# atxpd.net
KiCad netlist of a schematic drawn in EAGLE
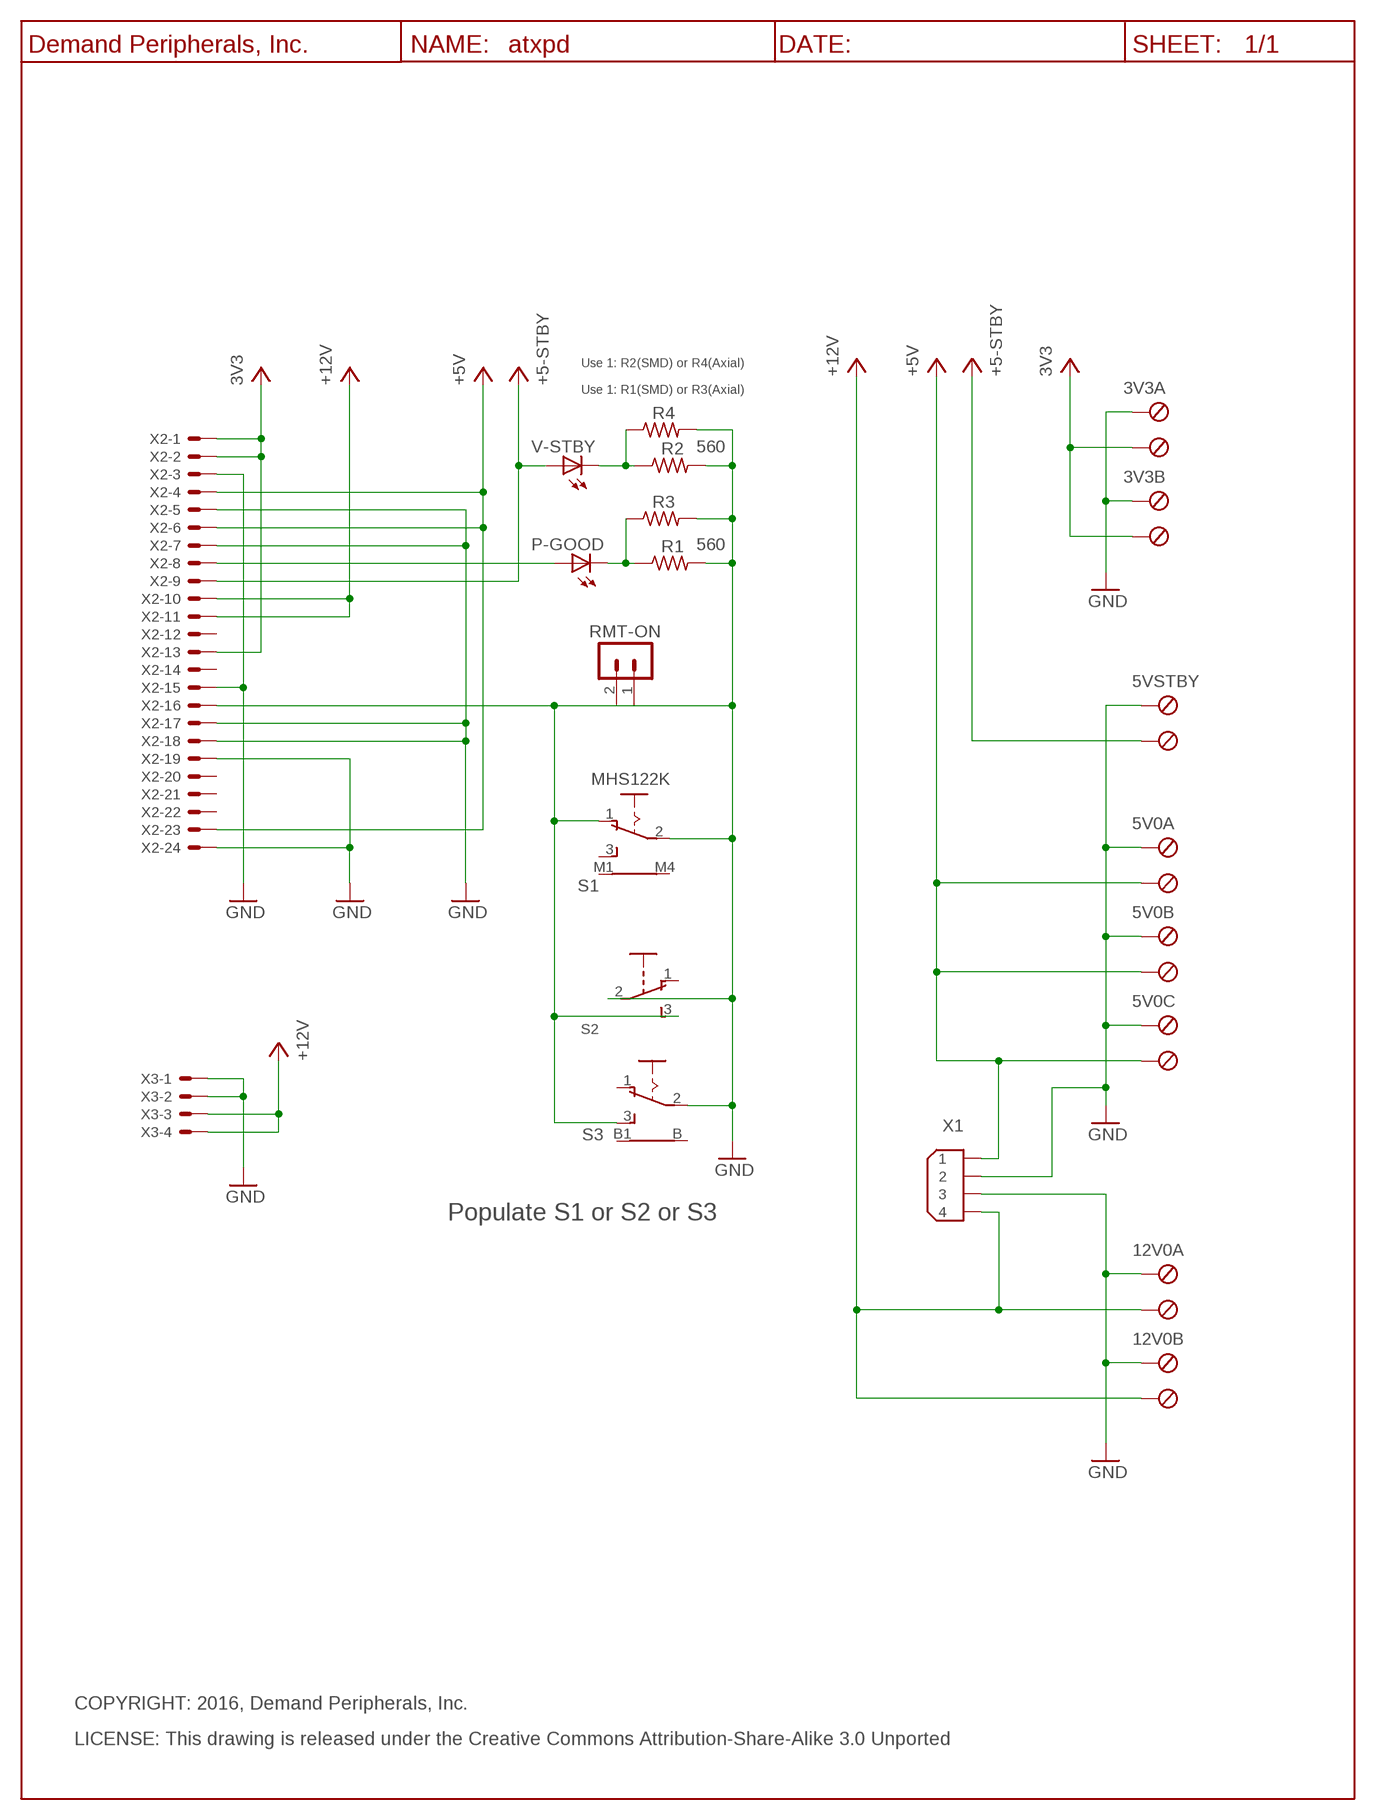
[diagram p0: schematic, sheet 1]

(export (version "E")
  (design (tool "Eeschema 10.0.6"))
  (components
    (comp (ref "3V3A")
      (value "TBLK-5.08-X2")
      (footprint "eagle-import:TBLK-5.08-X2")
      (libsource (lib "eagle-import") (part "TBLK-5.08-X2"))
    )
    (comp (ref "3V3B")
      (value "TBLK-5.08-X2")
      (footprint "eagle-import:TBLK-5.08-X2")
      (libsource (lib "eagle-import") (part "TBLK-5.08-X2"))
    )
    (comp (ref "5V0A")
      (value "TBLK-5.08-X2")
      (footprint "eagle-import:TBLK-5.08-X2")
      (libsource (lib "eagle-import") (part "TBLK-5.08-X2"))
    )
    (comp (ref "5V0B")
      (value "TBLK-5.08-X2")
      (footprint "eagle-import:TBLK-5.08-X2")
      (libsource (lib "eagle-import") (part "TBLK-5.08-X2"))
    )
    (comp (ref "5V0C")
      (value "TBLK-5.08-X2")
      (footprint "eagle-import:TBLK-5.08-X2")
      (libsource (lib "eagle-import") (part "TBLK-5.08-X2"))
    )
    (comp (ref "5VSTBY")
      (value "TBLK-5.08-X2")
      (footprint "eagle-import:TBLK-5.08-X2")
      (libsource (lib "eagle-import") (part "TBLK-5.08-X2"))
    )
    (comp (ref "12V0A")
      (value "TBLK-5.08-X2")
      (footprint "eagle-import:TBLK-5.08-X2")
      (libsource (lib "eagle-import") (part "TBLK-5.08-X2"))
    )
    (comp (ref "12V0B")
      (value "TBLK-5.08-X2")
      (footprint "eagle-import:TBLK-5.08-X2")
      (libsource (lib "eagle-import") (part "TBLK-5.08-X2"))
    )
    (comp (ref "P-GOOD")
      (value "3mm_LED")
      (footprint "eagle-import:LED5MM")
      (libsource (lib "eagle-import") (part "LED-5MM-RED"))
    )
    (comp (ref "R1")
      (value "560")
      (footprint "eagle-import:R0603")
      (libsource (lib "eagle-import") (part "R560_R0603"))
    )
    (comp (ref "R2")
      (value "560")
      (footprint "eagle-import:R0603")
      (libsource (lib "eagle-import") (part "R560_R0603"))
    )
    (comp (ref "R3")
      (value "560")
      (footprint "eagle-import:R4TENTHS")
      (libsource (lib "eagle-import") (part "R560_"))
    )
    (comp (ref "R4")
      (value "560")
      (footprint "eagle-import:R4TENTHS")
      (libsource (lib "eagle-import") (part "R560_"))
    )
    (comp (ref "RMT-ON")
      (value "PinHdr254-2")
      (footprint "eagle-import:HDR-2X1")
      (libsource (lib "eagle-import") (part "HDR-2X1-LCK"))
    )
    (comp (ref "S1")
      (value "MHS122K")
      (footprint "eagle-import:MHS122K")
      (libsource (lib "eagle-import") (part "MHS122K"))
    )
    (comp (ref "S2")
      (value "TINYTOGGLE-SPDT-TH")
      (footprint "eagle-import:SPDT-TENTHINCH")
      (libsource (lib "eagle-import") (part "TINYTOGGLE-SPDT-TH"))
    )
    (comp (ref "S3")
      (value "Vert_SW(Option)")
      (footprint "eagle-import:TOGGLE_SPDT_PC")
      (libsource (lib "eagle-import") (part "TOGGLE_SPDT_PC"))
    )
    (comp (ref "U$1")
      (value "DP_FRAME_P")
      (footprint "eagle-import:LETTER_P")
      (libsource (lib "eagle-import") (part "DP_FRAME_P"))
    )
    (comp (ref "V-STBY")
      (value "3mm_LED")
      (footprint "eagle-import:LED5MM")
      (libsource (lib "eagle-import") (part "LED-5MM-GRN"))
    )
    (comp (ref "X1")
      (value "9090-4V")
      (footprint "eagle-import:9090-4V")
      (libsource (lib "eagle-import") (part "9090-4V"))
    )
    (comp (ref "X2")
      (value "ATX_Std")
      (footprint "eagle-import:5566-24MOD")
      (libsource (lib "eagle-import") (part "5566-24MOD"))
    )
    (comp (ref "X3")
      (value "ATX_Plus4")
      (footprint "eagle-import:5566-4MOD")
      (libsource (lib "eagle-import") (part "5566-4MOD"))
    )
  )
  (nets
    (net (code "1") (name "+5-STBY") (class "Default")
      (node (ref "5VSTBY") (pin "2") (pinfunction "KL1_2") (pintype "passive"))
      (node (ref "V-STBY") (pin "A") (pinfunction "A_A") (pintype "passive"))
      (node (ref "X2") (pin "9") (pinfunction "S_9") (pintype "passive"))
    )
    (net (code "2") (name "+5V") (class "Default")
      (node (ref "5V0A") (pin "2") (pinfunction "KL1_2") (pintype "passive"))
      (node (ref "5V0B") (pin "2") (pinfunction "KL1_2") (pintype "passive"))
      (node (ref "5V0C") (pin "2") (pinfunction "KL1_2") (pintype "passive"))
      (node (ref "X1") (pin "1") (pinfunction "1_1") (pintype "passive"))
      (node (ref "X2") (pin "23") (pinfunction "S_23") (pintype "passive"))
      (node (ref "X2") (pin "4") (pinfunction "S_4") (pintype "passive"))
      (node (ref "X2") (pin "6") (pinfunction "S_6") (pintype "passive"))
    )
    (net (code "3") (name "+12V") (class "Default")
      (node (ref "12V0A") (pin "2") (pinfunction "KL1_2") (pintype "passive"))
      (node (ref "12V0B") (pin "2") (pinfunction "KL1_2") (pintype "passive"))
      (node (ref "X1") (pin "4") (pinfunction "4_4") (pintype "passive"))
      (node (ref "X2") (pin "10") (pinfunction "S_10") (pintype "passive"))
      (node (ref "X2") (pin "11") (pinfunction "S_11") (pintype "passive"))
      (node (ref "X3") (pin "3") (pinfunction "S_3") (pintype "passive"))
      (node (ref "X3") (pin "4") (pinfunction "S_4") (pintype "passive"))
    )
    (net (code "4") (name "3V3") (class "Default")
      (node (ref "3V3A") (pin "2") (pinfunction "KL1_2") (pintype "passive"))
      (node (ref "3V3B") (pin "2") (pinfunction "KL1_2") (pintype "passive"))
      (node (ref "X2") (pin "1") (pinfunction "S_1") (pintype "passive"))
      (node (ref "X2") (pin "13") (pinfunction "S_13") (pintype "passive"))
      (node (ref "X2") (pin "2") (pinfunction "S_2") (pintype "passive"))
    )
    (net (code "5") (name "GND") (class "Default")
      (node (ref "12V0A") (pin "1") (pinfunction "KL_1") (pintype "passive"))
      (node (ref "12V0B") (pin "1") (pinfunction "KL_1") (pintype "passive"))
      (node (ref "3V3A") (pin "1") (pinfunction "KL_1") (pintype "passive"))
      (node (ref "3V3B") (pin "1") (pinfunction "KL_1") (pintype "passive"))
      (node (ref "5V0A") (pin "1") (pinfunction "KL_1") (pintype "passive"))
      (node (ref "5V0B") (pin "1") (pinfunction "KL_1") (pintype "passive"))
      (node (ref "5V0C") (pin "1") (pinfunction "KL_1") (pintype "passive"))
      (node (ref "5VSTBY") (pin "1") (pinfunction "KL_1") (pintype "passive"))
      (node (ref "R1") (pin "2") (pinfunction "2_2") (pintype "passive"))
      (node (ref "R2") (pin "2") (pinfunction "2_2") (pintype "passive"))
      (node (ref "R3") (pin "2") (pinfunction "2_2") (pintype "passive"))
      (node (ref "R4") (pin "2") (pinfunction "2_2") (pintype "passive"))
      (node (ref "RMT-ON") (pin "2") (pinfunction "1_2") (pintype "passive"))
      (node (ref "S1") (pin "2") (pinfunction "P_2") (pintype "passive"))
      (node (ref "S2") (pin "2") (pinfunction "2_2") (pintype "passive"))
      (node (ref "S3") (pin "2") (pinfunction "P_2") (pintype "passive"))
      (node (ref "X1") (pin "2") (pinfunction "2_2") (pintype "passive"))
      (node (ref "X1") (pin "3") (pinfunction "3_3") (pintype "passive"))
      (node (ref "X2") (pin "15") (pinfunction "S_15") (pintype "passive"))
      (node (ref "X2") (pin "17") (pinfunction "S_17") (pintype "passive"))
      (node (ref "X2") (pin "18") (pinfunction "S_18") (pintype "passive"))
      (node (ref "X2") (pin "19") (pinfunction "S_19") (pintype "passive"))
      (node (ref "X2") (pin "24") (pinfunction "S_24") (pintype "passive"))
      (node (ref "X2") (pin "3") (pinfunction "S_3") (pintype "passive"))
      (node (ref "X2") (pin "5") (pinfunction "S_5") (pintype "passive"))
      (node (ref "X2") (pin "7") (pinfunction "S_7") (pintype "passive"))
      (node (ref "X3") (pin "1") (pinfunction "S_1") (pintype "passive"))
      (node (ref "X3") (pin "2") (pinfunction "S_2") (pintype "passive"))
    )
    (net (code "6") (name "Net-(P-GOOD-PadC)") (class "Default")
      (node (ref "P-GOOD") (pin "C") (pinfunction "C_C") (pintype "passive"))
      (node (ref "R1") (pin "1") (pinfunction "1_1") (pintype "passive"))
      (node (ref "R3") (pin "1") (pinfunction "1_1") (pintype "passive"))
    )
    (net (code "7") (name "Net-(R2-Pad1)") (class "Default")
      (node (ref "R2") (pin "1") (pinfunction "1_1") (pintype "passive"))
      (node (ref "R4") (pin "1") (pinfunction "1_1") (pintype "passive"))
      (node (ref "V-STBY") (pin "C") (pinfunction "C_C") (pintype "passive"))
    )
    (net (code "8") (name "Net-(RMT-ON-2)") (class "Default")
      (node (ref "RMT-ON") (pin "1") (pinfunction "2_1") (pintype "passive"))
      (node (ref "S1") (pin "1") (pinfunction "O_1") (pintype "passive"))
      (node (ref "S2") (pin "3") (pinfunction "3_3") (pintype "passive"))
      (node (ref "S3") (pin "3") (pinfunction "S_3") (pintype "passive"))
      (node (ref "X2") (pin "16") (pinfunction "S_16") (pintype "passive"))
    )
    (net (code "9") (name "Net-(X2W-S)") (class "Default")
      (node (ref "P-GOOD") (pin "A") (pinfunction "A_A") (pintype "passive"))
      (node (ref "X2") (pin "8") (pinfunction "S_8") (pintype "passive"))
    )
    (net (code "10") (name "unconnected-(S1-B-PadM4)") (class "Default")
      (node (ref "S1") (pin "M4") (pinfunction "B_M4") (pintype "passive"))
    )
    (net (code "11") (name "unconnected-(S1-B1-PadM1)") (class "Default")
      (node (ref "S1") (pin "M1") (pinfunction "B1_M1") (pintype "passive"))
    )
    (net (code "12") (name "unconnected-(S1-S-Pad3)") (class "Default")
      (node (ref "S1") (pin "3") (pinfunction "S_3") (pintype "passive"))
    )
    (net (code "13") (name "unconnected-(S2-Pad1)") (class "Default")
      (node (ref "S2") (pin "1") (pinfunction "1_1") (pintype "passive"))
    )
    (net (code "14") (name "unconnected-(S3-O-Pad1)") (class "Default")
      (node (ref "S3") (pin "1") (pinfunction "O_1") (pintype "passive"))
    )
    (net (code "15") (name "unconnected-(S3-PadB)") (class "Default")
      (node (ref "S3") (pin "B") (pinfunction "B_B") (pintype "passive"))
    )
    (net (code "16") (name "unconnected-(S3-PadB1)") (class "Default")
      (node (ref "S3") (pin "B1") (pinfunction "B1_B1") (pintype "passive"))
    )
    (net (code "17") (name "unconnected-(X2D-S-Pad12)") (class "Default")
      (node (ref "X2") (pin "12") (pinfunction "S_12") (pintype "passive"))
    )
    (net (code "18") (name "unconnected-(X2F-S-Pad14)") (class "Default")
      (node (ref "X2") (pin "14") (pinfunction "S_14") (pintype "passive"))
    )
    (net (code "19") (name "unconnected-(X2M-S-Pad20)") (class "Default")
      (node (ref "X2") (pin "20") (pinfunction "S_20") (pintype "passive"))
    )
    (net (code "20") (name "unconnected-(X2N-S-Pad21)") (class "Default")
      (node (ref "X2") (pin "21") (pinfunction "S_21") (pintype "passive"))
    )
    (net (code "21") (name "unconnected-(X2O-S-Pad22)") (class "Default")
      (node (ref "X2") (pin "22") (pinfunction "S_22") (pintype "passive"))
    )
  )
)
